# BioZ_Sensor.net
KiCad netlist of a schematic drawn in Altium Designer
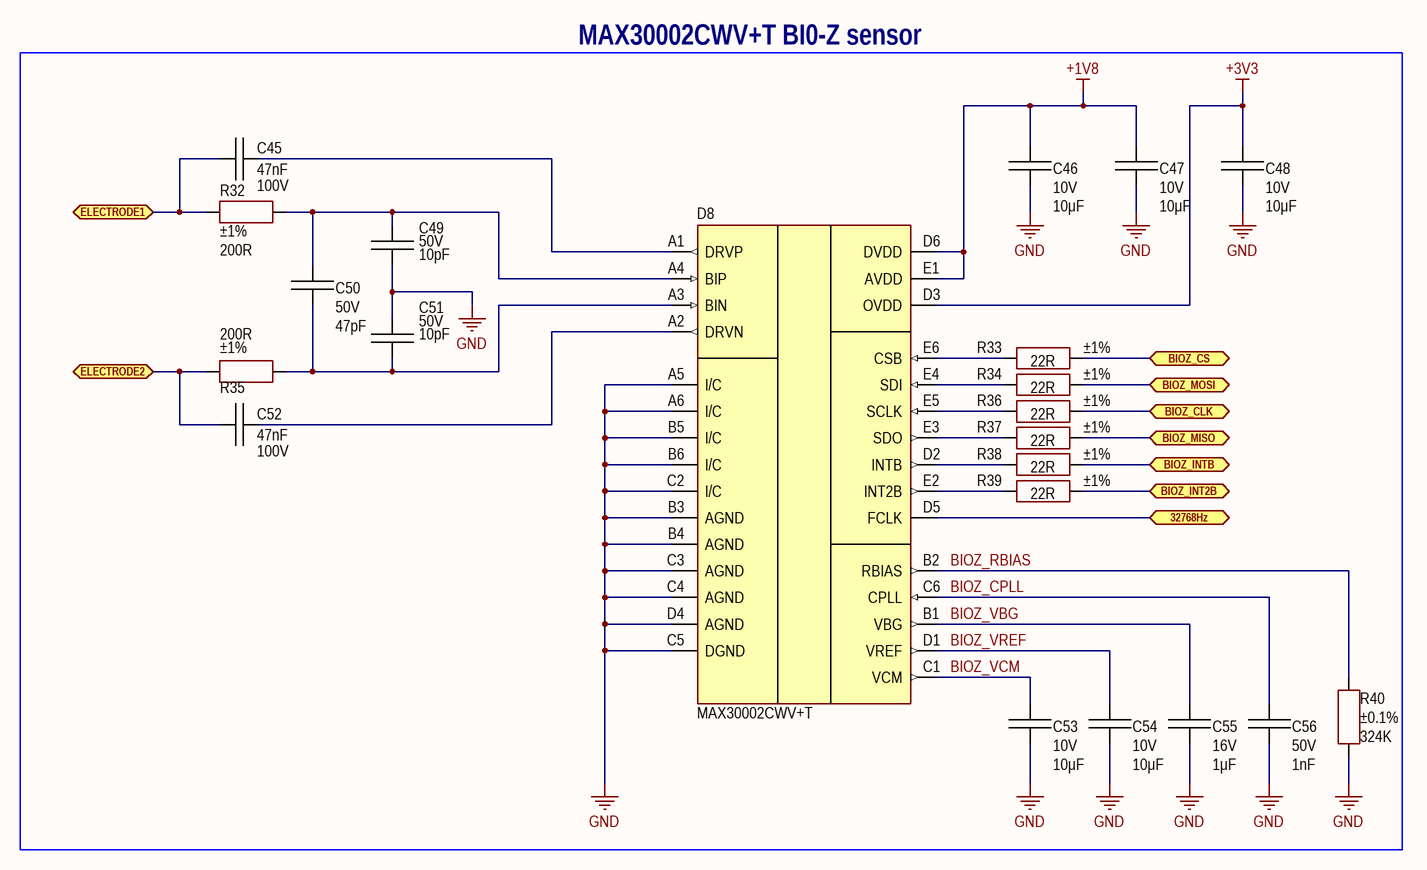
[diagram p0: BioZ_Sensor.SchDoc]

(export (version "E")
  (design (tool "Eeschema 10.0.6"))
  (components
    (comp (ref "C45")
      (value "47nF")
      (footprint "CAP: 0805")
      (description "0.047 µF ±10% 100V Ceramic Capacitor X7R 0805 (2012 Metric)")
      (fields
        (field (name "MANUFACTURER") "Yageo")
        (field (name "PARTNUMBER") "CC0805KKX7R0BB473")
        (field (name "VOLTAGE") "100V")
      )
      (libsource (lib "capacitor") (part "Ceramic_0805"))
    )
    (comp (ref "C46")
      (value "10μF")
      (footprint "CAP: 0805")
      (description "10 µF ±10% 10V Ceramic Capacitor X7R 0805 (2012 Metric)")
      (fields
        (field (name "MANUFACTURER") "Yageo")
        (field (name "PARTNUMBER") "CC0805KFX7R6BB106")
        (field (name "VOLTAGE") "10V")
      )
      (libsource (lib "capacitor") (part "Ceramic_0805"))
    )
    (comp (ref "C47")
      (value "10μF")
      (footprint "CAP: 0805")
      (description "10 µF ±10% 10V Ceramic Capacitor X7R 0805 (2012 Metric)")
      (fields
        (field (name "MANUFACTURER") "Yageo")
        (field (name "PARTNUMBER") "CC0805KFX7R6BB106")
        (field (name "VOLTAGE") "10V")
      )
      (libsource (lib "capacitor") (part "Ceramic_0805"))
    )
    (comp (ref "C48")
      (value "10μF")
      (footprint "CAP: 0805")
      (description "10 µF ±10% 10V Ceramic Capacitor X7R 0805 (2012 Metric)")
      (fields
        (field (name "MANUFACTURER") "Yageo")
        (field (name "PARTNUMBER") "CC0805KFX7R6BB106")
        (field (name "VOLTAGE") "10V")
      )
      (libsource (lib "capacitor") (part "Ceramic_0805"))
    )
    (comp (ref "C49")
      (value "10pF")
      (footprint "CAP: 0805")
      (description "10 pF ±1% 50V Ceramic Capacitor C0G, NP0 0805 (2012 Metric)")
      (fields
        (field (name "MANUFACTURER") "Yageo")
        (field (name "PARTNUMBER") "CC0805FRNPO9BN100")
        (field (name "VOLTAGE") "50V")
      )
      (libsource (lib "capacitor") (part "Ceramic_0805"))
    )
    (comp (ref "C50")
      (value "47pF")
      (footprint "CAP: 0805")
      (description "47 pF ±5% 50V Ceramic Capacitor C0G, NP0 0805 (2012 Metric)")
      (fields
        (field (name "MANUFACTURER") "Yageo")
        (field (name "PARTNUMBER") "CC0805JRNPO9BN470")
        (field (name "VOLTAGE") "50V")
      )
      (libsource (lib "capacitor") (part "Ceramic_0805"))
    )
    (comp (ref "C51")
      (value "10pF")
      (footprint "CAP: 0805")
      (description "10 pF ±1% 50V Ceramic Capacitor C0G, NP0 0805 (2012 Metric)")
      (fields
        (field (name "MANUFACTURER") "Yageo")
        (field (name "PARTNUMBER") "CC0805FRNPO9BN100")
        (field (name "VOLTAGE") "50V")
      )
      (libsource (lib "capacitor") (part "Ceramic_0805"))
    )
    (comp (ref "C52")
      (value "47nF")
      (footprint "CAP: 0805")
      (description "0.047 µF ±10% 100V Ceramic Capacitor X7R 0805 (2012 Metric)")
      (fields
        (field (name "MANUFACTURER") "Yageo")
        (field (name "PARTNUMBER") "CC0805KKX7R0BB473")
        (field (name "VOLTAGE") "100V")
      )
      (libsource (lib "capacitor") (part "Ceramic_0805"))
    )
    (comp (ref "C53")
      (value "10μF")
      (footprint "CAP: 0805")
      (description "10 µF ±10% 10V Ceramic Capacitor X7R 0805 (2012 Metric)")
      (fields
        (field (name "MANUFACTURER") "Yageo")
        (field (name "PARTNUMBER") "CC0805KFX7R6BB106")
        (field (name "VOLTAGE") "10V")
      )
      (libsource (lib "capacitor") (part "Ceramic_0805"))
    )
    (comp (ref "C54")
      (value "10μF")
      (footprint "CAP: 0805")
      (description "10 µF ±10% 10V Ceramic Capacitor X7R 0805 (2012 Metric)")
      (fields
        (field (name "MANUFACTURER") "Yageo")
        (field (name "PARTNUMBER") "CC0805KFX7R6BB106")
        (field (name "VOLTAGE") "10V")
      )
      (libsource (lib "capacitor") (part "Ceramic_0805"))
    )
    (comp (ref "C55")
      (value "1μF")
      (footprint "CAP: 0805")
      (description "1 µF ±10% 16V Ceramic Capacitor X7R 0805 (2012 Metric)")
      (fields
        (field (name "MANUFACTURER") "Yageo")
        (field (name "PARTNUMBER") "CC0805KKX7R7BB105")
        (field (name "VOLTAGE") "16V")
      )
      (libsource (lib "capacitor") (part "Ceramic_0805"))
    )
    (comp (ref "C56")
      (value "1nF")
      (footprint "CAP: 0805")
      (description "1000 pF ±5% 50V Ceramic Capacitor C0G, NP0 0805 (2012 Metric)")
      (fields
        (field (name "MANUFACTURER") "Yageo")
        (field (name "PARTNUMBER") "CC0805JRNPO9BN102")
        (field (name "VOLTAGE") "50V")
      )
      (libsource (lib "capacitor") (part "Ceramic_0805"))
    )
    (comp (ref "D8")
      (value "~")
      (footprint "IC: 30-WLP")
      (description "Biopotential and Bioimpedance sensor")
      (fields (field (name "MANUFACTURER") "Maxim Integrated") (field (name "PARTNUMBER") "MAX30002CWV+T"))
      (libsource (lib "MyLib") (part "MAX30002CWV+T"))
    )
    (comp (ref "R32")
      (value "200R")
      (footprint "RES: 0805")
      (description "200 Ohms ±1% 0.125W, 1/8W Chip Resistor 0805 (2012 Metric) Moisture Resistant Thick Film")
      (fields
        (field (name "MANUFACTURER") "Yageo")
        (field (name "PARTNUMBER") "RC0805FR-07200RL")
        (field (name "TOLERANCE") "±1%")
      )
      (libsource (lib "") (part "Resistor_0805_1"))
    )
    (comp (ref "R33")
      (value "22R")
      (footprint "RES: 0805")
      (description "22 Ohms ±1% 0.125W, 1/8W Chip Resistor 0805 (2012 Metric) Moisture Resistant Thick Film")
      (fields
        (field (name "MANUFACTURER") "Yageo")
        (field (name "PARTNUMBER") "RC0805FR-0722RL")
        (field (name "TOLERANCE") "±1%")
      )
      (libsource (lib "resistor") (part "Resistor_0805"))
    )
    (comp (ref "R34")
      (value "22R")
      (footprint "RES: 0805")
      (description "22 Ohms ±1% 0.125W, 1/8W Chip Resistor 0805 (2012 Metric) Moisture Resistant Thick Film")
      (fields
        (field (name "MANUFACTURER") "Yageo")
        (field (name "PARTNUMBER") "RC0805FR-0722RL")
        (field (name "TOLERANCE") "±1%")
      )
      (libsource (lib "resistor") (part "Resistor_0805"))
    )
    (comp (ref "R35")
      (value "200R")
      (footprint "RES: 0805")
      (description "200 Ohms ±1% 0.125W, 1/8W Chip Resistor 0805 (2012 Metric) Moisture Resistant Thick Film")
      (fields
        (field (name "MANUFACTURER") "Yageo")
        (field (name "PARTNUMBER") "RC0805FR-07200RL")
        (field (name "TOLERANCE") "±1%")
      )
      (libsource (lib "") (part "Resistor_0805_1"))
    )
    (comp (ref "R36")
      (value "22R")
      (footprint "RES: 0805")
      (description "22 Ohms ±1% 0.125W, 1/8W Chip Resistor 0805 (2012 Metric) Moisture Resistant Thick Film")
      (fields
        (field (name "MANUFACTURER") "Yageo")
        (field (name "PARTNUMBER") "RC0805FR-0722RL")
        (field (name "TOLERANCE") "±1%")
      )
      (libsource (lib "resistor") (part "Resistor_0805"))
    )
    (comp (ref "R37")
      (value "22R")
      (footprint "RES: 0805")
      (description "22 Ohms ±1% 0.125W, 1/8W Chip Resistor 0805 (2012 Metric) Moisture Resistant Thick Film")
      (fields
        (field (name "MANUFACTURER") "Yageo")
        (field (name "PARTNUMBER") "RC0805FR-0722RL")
        (field (name "TOLERANCE") "±1%")
      )
      (libsource (lib "resistor") (part "Resistor_0805"))
    )
    (comp (ref "R38")
      (value "22R")
      (footprint "RES: 0805")
      (description "22 Ohms ±1% 0.125W, 1/8W Chip Resistor 0805 (2012 Metric) Moisture Resistant Thick Film")
      (fields
        (field (name "MANUFACTURER") "Yageo")
        (field (name "PARTNUMBER") "RC0805FR-0722RL")
        (field (name "TOLERANCE") "±1%")
      )
      (libsource (lib "resistor") (part "Resistor_0805"))
    )
    (comp (ref "R39")
      (value "22R")
      (footprint "RES: 0805")
      (description "22 Ohms ±1% 0.125W, 1/8W Chip Resistor 0805 (2012 Metric) Moisture Resistant Thick Film")
      (fields
        (field (name "MANUFACTURER") "Yageo")
        (field (name "PARTNUMBER") "RC0805FR-0722RL")
        (field (name "TOLERANCE") "±1%")
      )
      (libsource (lib "resistor") (part "Resistor_0805"))
    )
    (comp (ref "R40")
      (value "324K")
      (footprint "RES: 0805")
      (fields
        (field (name "MANUFACTURER") "TE Connectivity Passive Product")
        (field (name "PARTNUMBER") "RQ73C2A324KBTD")
        (field (name "VALUEMANUFACTURERPARTNUMBER") "Resistor film, 324K, ±0.1%, 0805, 0.125W, -55...+125°C")
        (field (name "TOLERANCE") "±0.1%")
      )
      (libsource (lib "") (part "Resistor_0805_2"))
    )
  )
  (nets
    (net (code "1") (name "+1V8") (class "Default")
      (node (ref "C46") (pin "2") (pinfunction "2_2") (pintype "passive"))
      (node (ref "C47") (pin "2") (pinfunction "2_2") (pintype "passive"))
      (node (ref "D8") (pin "D6") (pinfunction "DVDD_D6") (pintype "power_in"))
      (node (ref "D8") (pin "E1") (pinfunction "AVDD_E1") (pintype "power_in"))
    )
    (net (code "2") (name "+3V3") (class "Default")
      (node (ref "C48") (pin "2") (pinfunction "2_2") (pintype "passive"))
      (node (ref "D8") (pin "D3") (pinfunction "OVDD_D3") (pintype "power_in"))
    )
    (net (code "3") (name "/32768Hz") (class "Default")
      (node (ref "D8") (pin "D5") (pinfunction "FCLK_D5") (pintype "passive"))
    )
    (net (code "4") (name "/BIOZ_CLK") (class "Default")
      (node (ref "R36") (pin "2") (pinfunction "2_2") (pintype "passive"))
    )
    (net (code "5") (name "/BIOZ_CPLL") (class "Default")
      (node (ref "C56") (pin "2") (pinfunction "2_2") (pintype "passive"))
      (node (ref "D8") (pin "C6") (pinfunction "CPLL_C6") (pintype "input"))
    )
    (net (code "6") (name "/BIOZ_CS") (class "Default")
      (node (ref "R33") (pin "2") (pinfunction "2_2") (pintype "passive"))
    )
    (net (code "7") (name "/BIOZ_INT2B") (class "Default")
      (node (ref "R39") (pin "2") (pinfunction "2_2") (pintype "passive"))
    )
    (net (code "8") (name "/BIOZ_INTB") (class "Default")
      (node (ref "R38") (pin "2") (pinfunction "2_2") (pintype "passive"))
    )
    (net (code "9") (name "/BIOZ_MISO") (class "Default")
      (node (ref "R37") (pin "2") (pinfunction "2_2") (pintype "passive"))
    )
    (net (code "10") (name "/BIOZ_MOSI") (class "Default")
      (node (ref "R34") (pin "2") (pinfunction "2_2") (pintype "passive"))
    )
    (net (code "11") (name "/BIOZ_RBIAS") (class "Default")
      (node (ref "D8") (pin "B2") (pinfunction "RBIAS_B2") (pintype "output"))
      (node (ref "R40") (pin "2") (pinfunction "2_2") (pintype "passive"))
    )
    (net (code "12") (name "/BIOZ_VBG") (class "Default")
      (node (ref "C55") (pin "2") (pinfunction "2_2") (pintype "passive"))
      (node (ref "D8") (pin "B1") (pinfunction "VBG_B1") (pintype "output"))
    )
    (net (code "13") (name "/BIOZ_VCM") (class "Default")
      (node (ref "C53") (pin "2") (pinfunction "2_2") (pintype "passive"))
      (node (ref "D8") (pin "C1") (pinfunction "VCM_C1") (pintype "output"))
    )
    (net (code "14") (name "/BIOZ_VREF") (class "Default")
      (node (ref "C54") (pin "2") (pinfunction "2_2") (pintype "passive"))
      (node (ref "D8") (pin "D1") (pinfunction "VREF_D1") (pintype "output"))
    )
    (net (code "15") (name "/ELECTRODE1") (class "Default")
      (node (ref "C45") (pin "2") (pinfunction "2_2") (pintype "passive"))
      (node (ref "R32") (pin "2") (pinfunction "2_2") (pintype "passive"))
    )
    (net (code "16") (name "/ELECTRODE2") (class "Default")
      (node (ref "C52") (pin "2") (pinfunction "2_2") (pintype "passive"))
      (node (ref "R35") (pin "2") (pinfunction "2_2") (pintype "passive"))
    )
    (net (code "17") (name "GND") (class "Default")
      (node (ref "C46") (pin "1") (pinfunction "1_1") (pintype "passive"))
      (node (ref "C47") (pin "1") (pinfunction "1_1") (pintype "passive"))
      (node (ref "C48") (pin "1") (pinfunction "1_1") (pintype "passive"))
      (node (ref "C49") (pin "1") (pinfunction "1_1") (pintype "passive"))
      (node (ref "C51") (pin "2") (pinfunction "2_2") (pintype "passive"))
      (node (ref "C53") (pin "1") (pinfunction "1_1") (pintype "passive"))
      (node (ref "C54") (pin "1") (pinfunction "1_1") (pintype "passive"))
      (node (ref "C55") (pin "1") (pinfunction "1_1") (pintype "passive"))
      (node (ref "C56") (pin "1") (pinfunction "1_1") (pintype "passive"))
      (node (ref "D8") (pin "A5") (pinfunction "I/C_A5") (pintype "power_in"))
      (node (ref "D8") (pin "A6") (pinfunction "I/C_A6") (pintype "power_in"))
      (node (ref "D8") (pin "B3") (pinfunction "AGND_B3") (pintype "power_in"))
      (node (ref "D8") (pin "B4") (pinfunction "AGND_B4") (pintype "power_in"))
      (node (ref "D8") (pin "B5") (pinfunction "I/C_B5") (pintype "power_in"))
      (node (ref "D8") (pin "B6") (pinfunction "I/C_B6") (pintype "power_in"))
      (node (ref "D8") (pin "C2") (pinfunction "I/C_C2") (pintype "power_in"))
      (node (ref "D8") (pin "C3") (pinfunction "AGND_C3") (pintype "power_in"))
      (node (ref "D8") (pin "C4") (pinfunction "AGND_C4") (pintype "power_in"))
      (node (ref "D8") (pin "C5") (pinfunction "DGND_C5") (pintype "power_in"))
      (node (ref "D8") (pin "D4") (pinfunction "AGND_D4") (pintype "power_in"))
      (node (ref "R40") (pin "1") (pinfunction "1_1") (pintype "passive"))
    )
    (net (code "18") (name "Net-(D8-BIN)") (class "Default")
      (node (ref "C50") (pin "1") (pinfunction "1_1") (pintype "passive"))
      (node (ref "C51") (pin "1") (pinfunction "1_1") (pintype "passive"))
      (node (ref "D8") (pin "A3") (pinfunction "BIN_A3") (pintype "input"))
      (node (ref "R35") (pin "1") (pinfunction "1_1") (pintype "passive"))
    )
    (net (code "19") (name "Net-(D8-BIP)") (class "Default")
      (node (ref "C49") (pin "2") (pinfunction "2_2") (pintype "passive"))
      (node (ref "C50") (pin "2") (pinfunction "2_2") (pintype "passive"))
      (node (ref "D8") (pin "A4") (pinfunction "BIP_A4") (pintype "input"))
      (node (ref "R32") (pin "1") (pinfunction "1_1") (pintype "passive"))
    )
    (net (code "20") (name "Net-(D8-CSB)") (class "Default")
      (node (ref "D8") (pin "E6") (pinfunction "CSB_E6") (pintype "input"))
      (node (ref "R33") (pin "1") (pinfunction "1_1") (pintype "passive"))
    )
    (net (code "21") (name "Net-(D8-DRVN)") (class "Default")
      (node (ref "C52") (pin "1") (pinfunction "1_1") (pintype "passive"))
      (node (ref "D8") (pin "A2") (pinfunction "DRVN_A2") (pintype "output"))
    )
    (net (code "22") (name "Net-(D8-DRVP)") (class "Default")
      (node (ref "C45") (pin "1") (pinfunction "1_1") (pintype "passive"))
      (node (ref "D8") (pin "A1") (pinfunction "DRVP_A1") (pintype "output"))
    )
    (net (code "23") (name "Net-(D8-INT2B)") (class "Default")
      (node (ref "D8") (pin "E2") (pinfunction "INT2B_E2") (pintype "output"))
      (node (ref "R39") (pin "1") (pinfunction "1_1") (pintype "passive"))
    )
    (net (code "24") (name "Net-(D8-INTB)") (class "Default")
      (node (ref "D8") (pin "D2") (pinfunction "INTB_D2") (pintype "output"))
      (node (ref "R38") (pin "1") (pinfunction "1_1") (pintype "passive"))
    )
    (net (code "25") (name "Net-(D8-SCLK)") (class "Default")
      (node (ref "D8") (pin "E5") (pinfunction "SCLK_E5") (pintype "input"))
      (node (ref "R36") (pin "1") (pinfunction "1_1") (pintype "passive"))
    )
    (net (code "26") (name "Net-(D8-SDI)") (class "Default")
      (node (ref "D8") (pin "E4") (pinfunction "SDI_E4") (pintype "input"))
      (node (ref "R34") (pin "1") (pinfunction "1_1") (pintype "passive"))
    )
    (net (code "27") (name "Net-(D8-SDO)") (class "Default")
      (node (ref "D8") (pin "E3") (pinfunction "SDO_E3") (pintype "output"))
      (node (ref "R37") (pin "1") (pinfunction "1_1") (pintype "passive"))
    )
  )
)
